# schematic.net
KiCad netlist of a schematic drawn in EAGLE
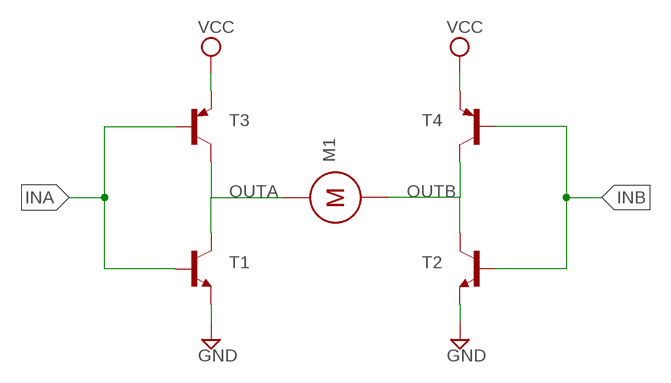
[diagram p0: schematic, sheet 1]

(export (version "E")
  (design (tool "Eeschema 10.0.6"))
  (components
    (comp (ref "M1")
      (value "308-100")
      (footprint "eagle-import:308-100")
      (libsource (lib "eagle-import") (part "308-100"))
    )
    (comp (ref "T1")
      (value "2N3904")
      (footprint "eagle-import:TO92")
      (libsource (lib "eagle-import") (part "2N3904"))
    )
    (comp (ref "T2")
      (value "2N3904")
      (footprint "eagle-import:TO92")
      (libsource (lib "eagle-import") (part "2N3904"))
    )
    (comp (ref "T3")
      (value "2N3906")
      (footprint "eagle-import:TO92")
      (libsource (lib "eagle-import") (part "2N3906"))
    )
    (comp (ref "T4")
      (value "2N3906")
      (footprint "eagle-import:TO92")
      (libsource (lib "eagle-import") (part "2N3906"))
    )
  )
  (nets
    (net (code "1") (name "/OUTA") (class "Default")
      (node (ref "M1") (pin "POS") (pinfunction "POS_POS") (pintype "bidirectional"))
      (node (ref "T1") (pin "1") (pinfunction "C_1") (pintype "passive"))
      (node (ref "T3") (pin "2") (pinfunction "C_2") (pintype "passive"))
    )
    (net (code "2") (name "/OUTB") (class "Default")
      (node (ref "M1") (pin "NEG") (pinfunction "NEG_NEG") (pintype "bidirectional"))
      (node (ref "T2") (pin "1") (pinfunction "C_1") (pintype "passive"))
      (node (ref "T4") (pin "2") (pinfunction "C_2") (pintype "passive"))
    )
    (net (code "3") (name "GND") (class "Default")
      (node (ref "T1") (pin "3") (pinfunction "E_3") (pintype "passive"))
      (node (ref "T2") (pin "3") (pinfunction "E_3") (pintype "passive"))
    )
    (net (code "4") (name "INA") (class "Default")
      (node (ref "T1") (pin "2") (pinfunction "B_2") (pintype "passive"))
      (node (ref "T3") (pin "1") (pinfunction "B_1") (pintype "passive"))
    )
    (net (code "5") (name "INB") (class "Default")
      (node (ref "T2") (pin "2") (pinfunction "B_2") (pintype "passive"))
      (node (ref "T4") (pin "1") (pinfunction "B_1") (pintype "passive"))
    )
    (net (code "6") (name "VCC") (class "Default")
      (node (ref "T3") (pin "3") (pinfunction "E_3") (pintype "passive"))
      (node (ref "T4") (pin "3") (pinfunction "E_3") (pintype "passive"))
    )
  )
)
